# SP26_brainstim3_Sig_Gen_1channel_schemat.net
KiCad netlist of a schematic drawn in EasyEDA
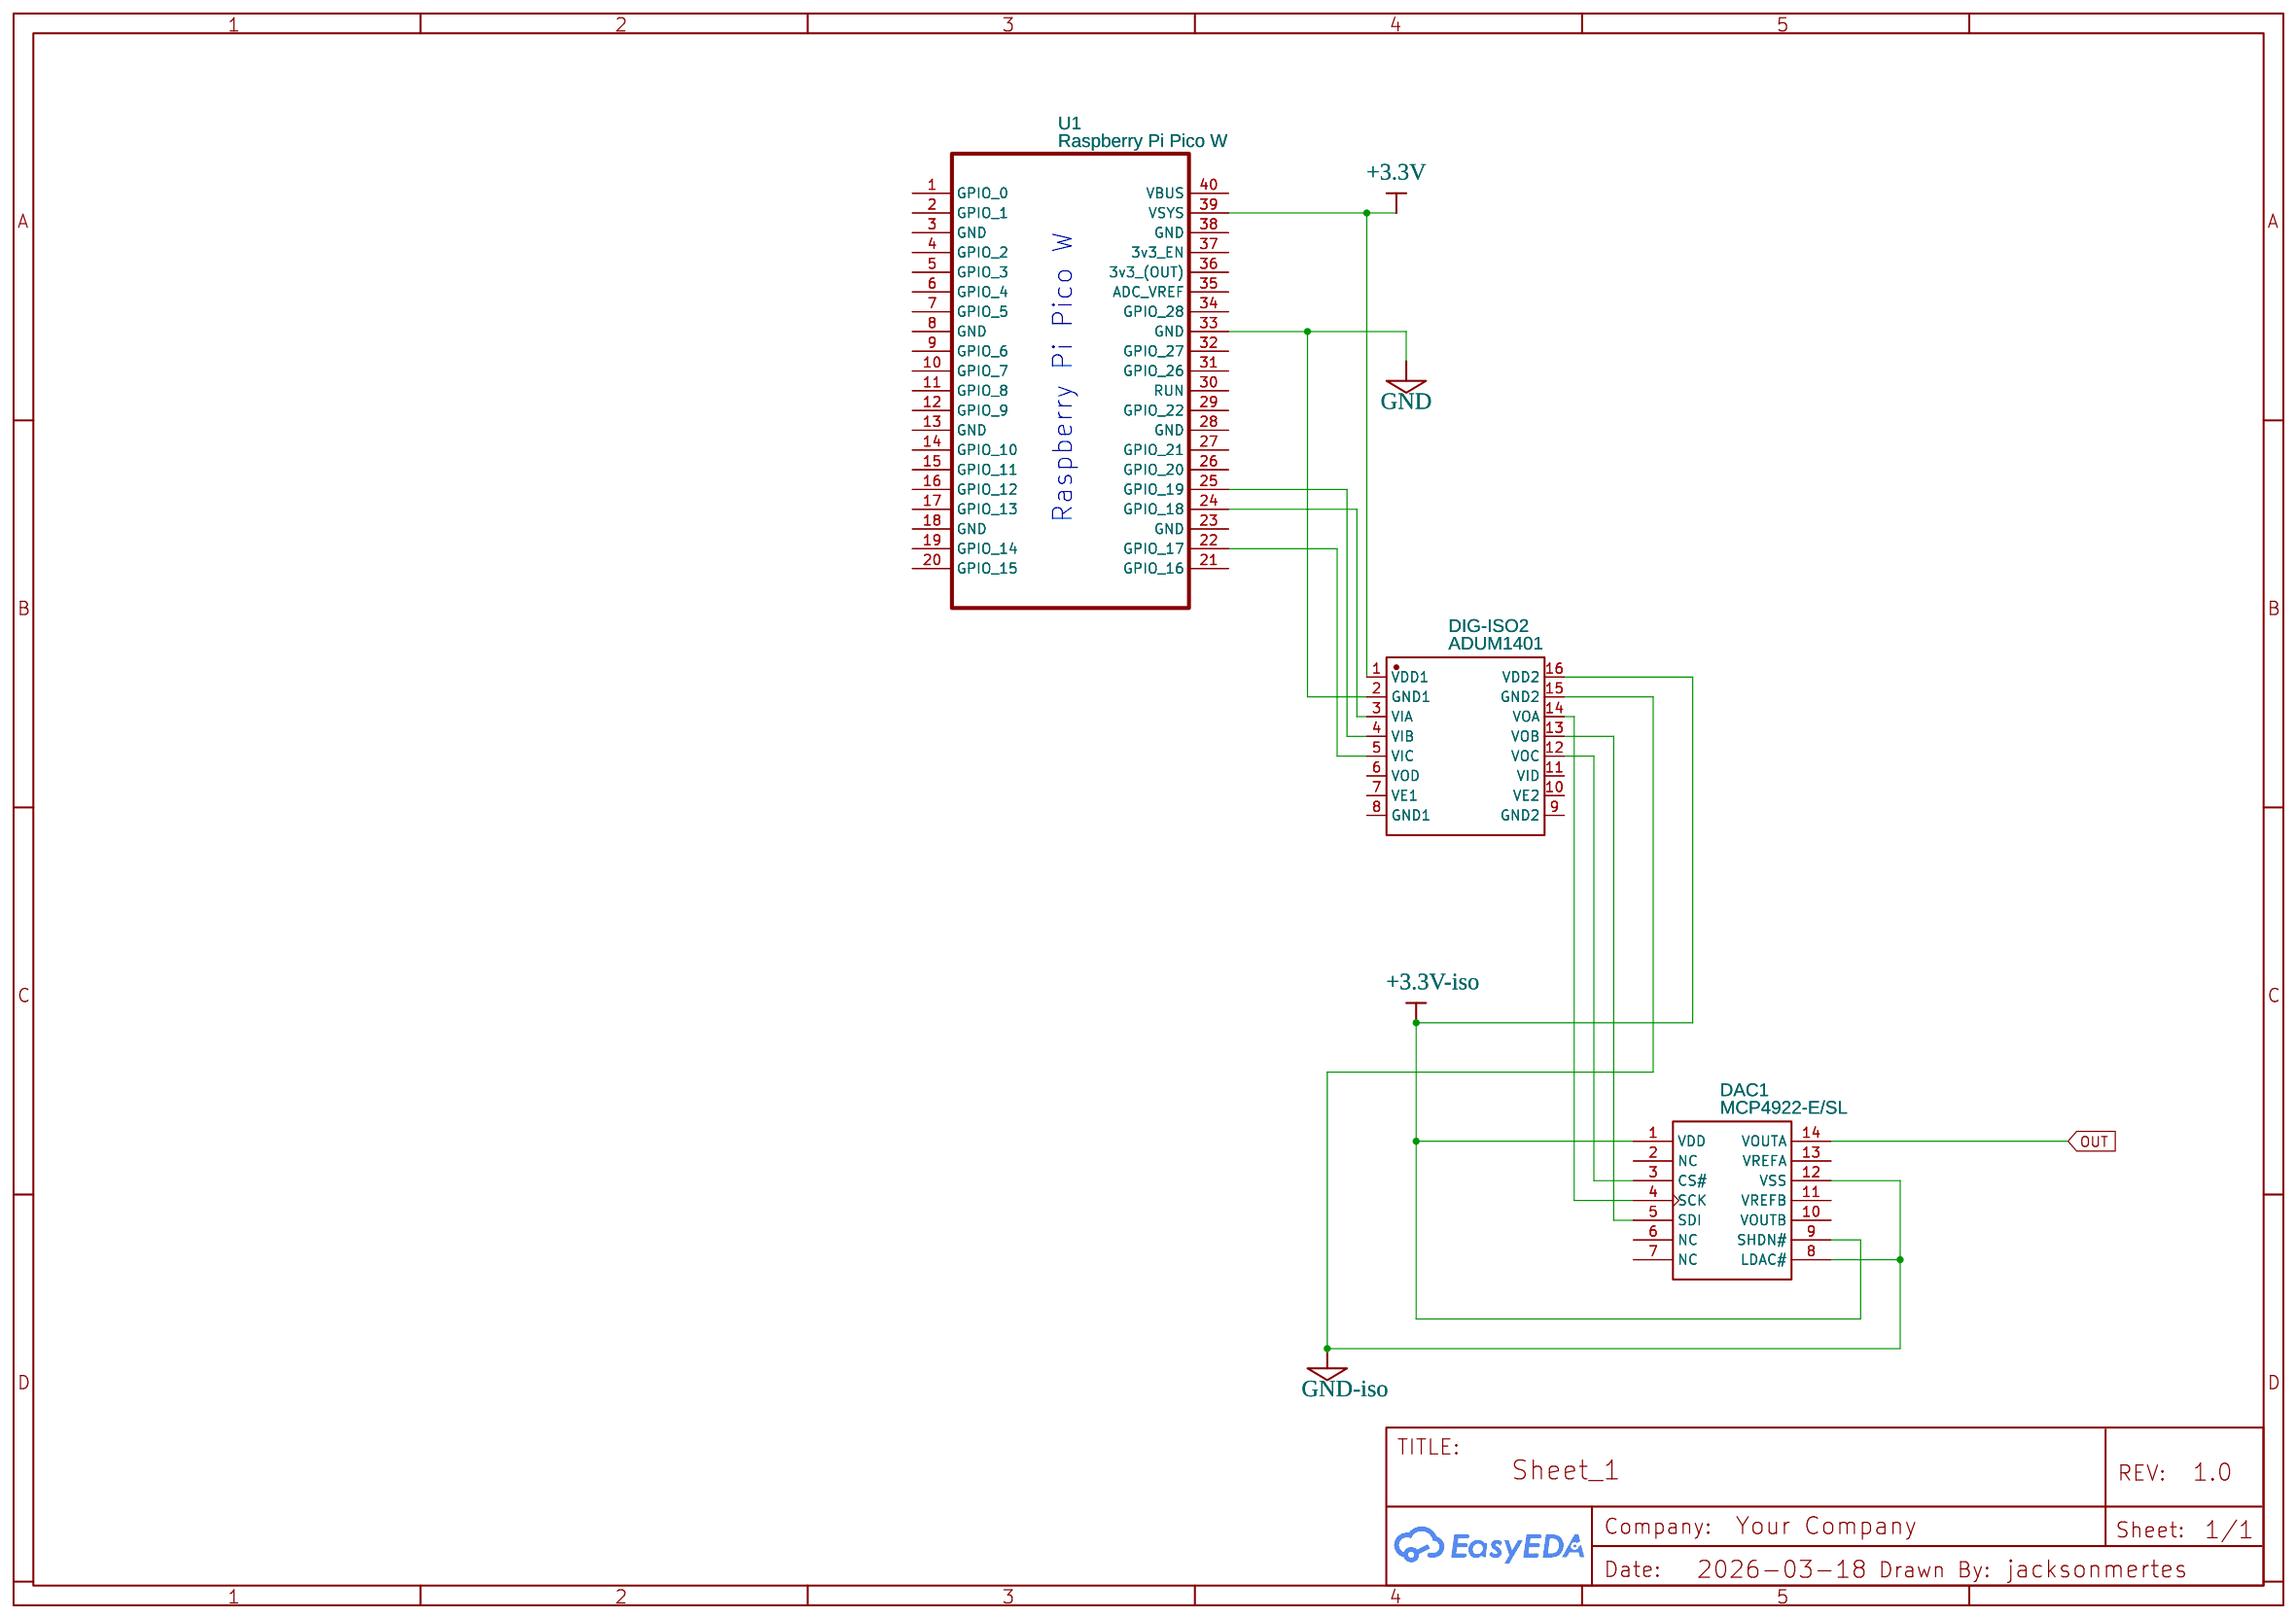
[diagram p0: schematic sheet]

(export (version "E")
  (design (tool "Eeschema 10.0.6"))
  (components
    (comp (ref "DAC1")
      (value "MCP4922-E/SL")
      (fields (field (name "Manufacturer") "MICROCHIP(美国微芯)"))
      (libsource (lib "") (part "MCP4922-E/SL"))
    )
    (comp (ref "DIG-ISO2")
      (value "ADUM1401")
      (fields
        (field (name "Manufacturer Part") "ADUM1401ARWZ-RL")
        (field (name "Manufacturer") "Analog Devices")
      )
      (libsource (lib "") (part "ADUM1401ARWZ-RL"))
    )
    (comp (ref "U1")
      (value "Raspberry Pi Pico W")
      (fields (field (name "Manufacturer Part") "PICO W") (field (name "Manufacturer") "Raspberry Pi"))
      (libsource (lib "") (part "Raspberry Pi Pico W"))
    )
  )
  (nets
    (net (code "1") (name "+3.3V") (class "Default")
      (node (ref "DIG-ISO2") (pin "1") (pinfunction "VDD1_1") (pintype "unspecified"))
      (node (ref "U1") (pin "39") (pinfunction "VSYS_39") (pintype "unspecified"))
    )
    (net (code "2") (name "+3.3V-iso") (class "Default")
      (node (ref "DAC1") (pin "1") (pinfunction "VDD_1") (pintype "passive"))
      (node (ref "DAC1") (pin "9") (pinfunction "SHDN#_9") (pintype "unspecified"))
      (node (ref "DIG-ISO2") (pin "16") (pinfunction "VDD2_16") (pintype "unspecified"))
    )
    (net (code "3") (name "GND") (class "Default")
      (node (ref "DIG-ISO2") (pin "2") (pinfunction "GND1_2") (pintype "unspecified"))
      (node (ref "U1") (pin "33") (pinfunction "GND_33") (pintype "unspecified"))
    )
    (net (code "4") (name "GND-iso") (class "Default")
      (node (ref "DAC1") (pin "12") (pinfunction "VSS_12") (pintype "passive"))
      (node (ref "DAC1") (pin "8") (pinfunction "LDAC#_8") (pintype "unspecified"))
      (node (ref "DIG-ISO2") (pin "15") (pinfunction "GND2_15") (pintype "unspecified"))
    )
    (net (code "5") (name "Net-(DAC1-CS#)") (class "Default")
      (node (ref "DAC1") (pin "3") (pinfunction "CS#_3") (pintype "unspecified"))
      (node (ref "DIG-ISO2") (pin "12") (pinfunction "VOC_12") (pintype "unspecified"))
    )
    (net (code "6") (name "Net-(DAC1-SCK)") (class "Default")
      (node (ref "DAC1") (pin "4") (pinfunction "SCK_4") (pintype "unspecified"))
      (node (ref "DIG-ISO2") (pin "14") (pinfunction "VOA_14") (pintype "unspecified"))
    )
    (net (code "7") (name "Net-(DAC1-SDI)") (class "Default")
      (node (ref "DAC1") (pin "5") (pinfunction "SDI_5") (pintype "unspecified"))
      (node (ref "DIG-ISO2") (pin "13") (pinfunction "VOB_13") (pintype "unspecified"))
    )
    (net (code "8") (name "Net-(DIG-ISO2-VIA)") (class "Default")
      (node (ref "DIG-ISO2") (pin "3") (pinfunction "VIA_3") (pintype "unspecified"))
      (node (ref "U1") (pin "24") (pinfunction "GPIO_18_24") (pintype "unspecified"))
    )
    (net (code "9") (name "Net-(DIG-ISO2-VIB)") (class "Default")
      (node (ref "DIG-ISO2") (pin "4") (pinfunction "VIB_4") (pintype "unspecified"))
      (node (ref "U1") (pin "25") (pinfunction "GPIO_19_25") (pintype "unspecified"))
    )
    (net (code "10") (name "Net-(DIG-ISO2-VIC)") (class "Default")
      (node (ref "DIG-ISO2") (pin "5") (pinfunction "VIC_5") (pintype "unspecified"))
      (node (ref "U1") (pin "22") (pinfunction "GPIO_17_22") (pintype "unspecified"))
    )
    (net (code "11") (name "OUT") (class "Default")
      (node (ref "DAC1") (pin "14") (pinfunction "VOUTA_14") (pintype "output"))
    )
    (net (code "12") (name "unconnected-(DAC1-NC-Pad2)") (class "Default")
      (node (ref "DAC1") (pin "2") (pinfunction "NC_2") (pintype "unspecified"))
    )
    (net (code "13") (name "unconnected-(DAC1-NC-Pad6)") (class "Default")
      (node (ref "DAC1") (pin "6") (pinfunction "NC_6") (pintype "unspecified"))
    )
    (net (code "14") (name "unconnected-(DAC1-NC-Pad7)") (class "Default")
      (node (ref "DAC1") (pin "7") (pinfunction "NC_7") (pintype "unspecified"))
    )
    (net (code "15") (name "unconnected-(DAC1-VOUTB-Pad10)") (class "Default")
      (node (ref "DAC1") (pin "10") (pinfunction "VOUTB_10") (pintype "output"))
    )
    (net (code "16") (name "unconnected-(DAC1-VREFA-Pad13)") (class "Default")
      (node (ref "DAC1") (pin "13") (pinfunction "VREFA_13") (pintype "unspecified"))
    )
    (net (code "17") (name "unconnected-(DAC1-VREFB-Pad11)") (class "Default")
      (node (ref "DAC1") (pin "11") (pinfunction "VREFB_11") (pintype "unspecified"))
    )
    (net (code "18") (name "unconnected-(DIG-ISO2-GND1-Pad8)") (class "Default")
      (node (ref "DIG-ISO2") (pin "8") (pinfunction "GND1_8") (pintype "unspecified"))
    )
    (net (code "19") (name "unconnected-(DIG-ISO2-GND2-Pad9)") (class "Default")
      (node (ref "DIG-ISO2") (pin "9") (pinfunction "GND2_9") (pintype "unspecified"))
    )
    (net (code "20") (name "unconnected-(DIG-ISO2-VE1-Pad7)") (class "Default")
      (node (ref "DIG-ISO2") (pin "7") (pinfunction "VE1_7") (pintype "unspecified"))
    )
    (net (code "21") (name "unconnected-(DIG-ISO2-VE2-Pad10)") (class "Default")
      (node (ref "DIG-ISO2") (pin "10") (pinfunction "VE2_10") (pintype "unspecified"))
    )
    (net (code "22") (name "unconnected-(DIG-ISO2-VID-Pad11)") (class "Default")
      (node (ref "DIG-ISO2") (pin "11") (pinfunction "VID_11") (pintype "unspecified"))
    )
    (net (code "23") (name "unconnected-(DIG-ISO2-VOD-Pad6)") (class "Default")
      (node (ref "DIG-ISO2") (pin "6") (pinfunction "VOD_6") (pintype "unspecified"))
    )
    (net (code "24") (name "unconnected-(U1-3v3_(OUT)-Pad36)") (class "Default")
      (node (ref "U1") (pin "36") (pinfunction "3v3_(OUT)_36") (pintype "unspecified"))
    )
    (net (code "25") (name "unconnected-(U1-3v3_EN-Pad37)") (class "Default")
      (node (ref "U1") (pin "37") (pinfunction "3v3_EN_37") (pintype "unspecified"))
    )
    (net (code "26") (name "unconnected-(U1-ADC_VREF-Pad35)") (class "Default")
      (node (ref "U1") (pin "35") (pinfunction "ADC_VREF_35") (pintype "unspecified"))
    )
    (net (code "27") (name "unconnected-(U1-GND-Pad3)") (class "Default")
      (node (ref "U1") (pin "3") (pinfunction "GND_3") (pintype "unspecified"))
    )
    (net (code "28") (name "unconnected-(U1-GND-Pad8)") (class "Default")
      (node (ref "U1") (pin "8") (pinfunction "GND_8") (pintype "unspecified"))
    )
    (net (code "29") (name "unconnected-(U1-GND-Pad13)") (class "Default")
      (node (ref "U1") (pin "13") (pinfunction "GND_13") (pintype "unspecified"))
    )
    (net (code "30") (name "unconnected-(U1-GND-Pad18)") (class "Default")
      (node (ref "U1") (pin "18") (pinfunction "GND_18") (pintype "unspecified"))
    )
    (net (code "31") (name "unconnected-(U1-GND-Pad23)") (class "Default")
      (node (ref "U1") (pin "23") (pinfunction "GND_23") (pintype "unspecified"))
    )
    (net (code "32") (name "unconnected-(U1-GND-Pad28)") (class "Default")
      (node (ref "U1") (pin "28") (pinfunction "GND_28") (pintype "unspecified"))
    )
    (net (code "33") (name "unconnected-(U1-GND-Pad38)") (class "Default")
      (node (ref "U1") (pin "38") (pinfunction "GND_38") (pintype "unspecified"))
    )
    (net (code "34") (name "unconnected-(U1-GPIO_0-Pad1)") (class "Default")
      (node (ref "U1") (pin "1") (pinfunction "GPIO_0_1") (pintype "unspecified"))
    )
    (net (code "35") (name "unconnected-(U1-GPIO_1-Pad2)") (class "Default")
      (node (ref "U1") (pin "2") (pinfunction "GPIO_1_2") (pintype "unspecified"))
    )
    (net (code "36") (name "unconnected-(U1-GPIO_2-Pad4)") (class "Default")
      (node (ref "U1") (pin "4") (pinfunction "GPIO_2_4") (pintype "unspecified"))
    )
    (net (code "37") (name "unconnected-(U1-GPIO_3-Pad5)") (class "Default")
      (node (ref "U1") (pin "5") (pinfunction "GPIO_3_5") (pintype "unspecified"))
    )
    (net (code "38") (name "unconnected-(U1-GPIO_4-Pad6)") (class "Default")
      (node (ref "U1") (pin "6") (pinfunction "GPIO_4_6") (pintype "unspecified"))
    )
    (net (code "39") (name "unconnected-(U1-GPIO_5-Pad7)") (class "Default")
      (node (ref "U1") (pin "7") (pinfunction "GPIO_5_7") (pintype "unspecified"))
    )
    (net (code "40") (name "unconnected-(U1-GPIO_6-Pad9)") (class "Default")
      (node (ref "U1") (pin "9") (pinfunction "GPIO_6_9") (pintype "unspecified"))
    )
    (net (code "41") (name "unconnected-(U1-GPIO_7-Pad10)") (class "Default")
      (node (ref "U1") (pin "10") (pinfunction "GPIO_7_10") (pintype "unspecified"))
    )
    (net (code "42") (name "unconnected-(U1-GPIO_8-Pad11)") (class "Default")
      (node (ref "U1") (pin "11") (pinfunction "GPIO_8_11") (pintype "unspecified"))
    )
    (net (code "43") (name "unconnected-(U1-GPIO_9-Pad12)") (class "Default")
      (node (ref "U1") (pin "12") (pinfunction "GPIO_9_12") (pintype "unspecified"))
    )
    (net (code "44") (name "unconnected-(U1-GPIO_10-Pad14)") (class "Default")
      (node (ref "U1") (pin "14") (pinfunction "GPIO_10_14") (pintype "unspecified"))
    )
    (net (code "45") (name "unconnected-(U1-GPIO_11-Pad15)") (class "Default")
      (node (ref "U1") (pin "15") (pinfunction "GPIO_11_15") (pintype "unspecified"))
    )
    (net (code "46") (name "unconnected-(U1-GPIO_12-Pad16)") (class "Default")
      (node (ref "U1") (pin "16") (pinfunction "GPIO_12_16") (pintype "unspecified"))
    )
    (net (code "47") (name "unconnected-(U1-GPIO_13-Pad17)") (class "Default")
      (node (ref "U1") (pin "17") (pinfunction "GPIO_13_17") (pintype "unspecified"))
    )
    (net (code "48") (name "unconnected-(U1-GPIO_14-Pad19)") (class "Default")
      (node (ref "U1") (pin "19") (pinfunction "GPIO_14_19") (pintype "unspecified"))
    )
    (net (code "49") (name "unconnected-(U1-GPIO_15-Pad20)") (class "Default")
      (node (ref "U1") (pin "20") (pinfunction "GPIO_15_20") (pintype "unspecified"))
    )
    (net (code "50") (name "unconnected-(U1-GPIO_16-Pad21)") (class "Default")
      (node (ref "U1") (pin "21") (pinfunction "GPIO_16_21") (pintype "unspecified"))
    )
    (net (code "51") (name "unconnected-(U1-GPIO_20-Pad26)") (class "Default")
      (node (ref "U1") (pin "26") (pinfunction "GPIO_20_26") (pintype "unspecified"))
    )
    (net (code "52") (name "unconnected-(U1-GPIO_21-Pad27)") (class "Default")
      (node (ref "U1") (pin "27") (pinfunction "GPIO_21_27") (pintype "unspecified"))
    )
    (net (code "53") (name "unconnected-(U1-GPIO_22-Pad29)") (class "Default")
      (node (ref "U1") (pin "29") (pinfunction "GPIO_22_29") (pintype "unspecified"))
    )
    (net (code "54") (name "unconnected-(U1-GPIO_26-Pad31)") (class "Default")
      (node (ref "U1") (pin "31") (pinfunction "GPIO_26_31") (pintype "unspecified"))
    )
    (net (code "55") (name "unconnected-(U1-GPIO_27-Pad32)") (class "Default")
      (node (ref "U1") (pin "32") (pinfunction "GPIO_27_32") (pintype "unspecified"))
    )
    (net (code "56") (name "unconnected-(U1-GPIO_28-Pad34)") (class "Default")
      (node (ref "U1") (pin "34") (pinfunction "GPIO_28_34") (pintype "unspecified"))
    )
    (net (code "57") (name "unconnected-(U1-RUN-Pad30)") (class "Default")
      (node (ref "U1") (pin "30") (pinfunction "RUN_30") (pintype "unspecified"))
    )
    (net (code "58") (name "unconnected-(U1-VBUS-Pad40)") (class "Default")
      (node (ref "U1") (pin "40") (pinfunction "VBUS_40") (pintype "unspecified"))
    )
  )
)
